# hub-proto02.net
KiCad netlist of a schematic drawn in EAGLE
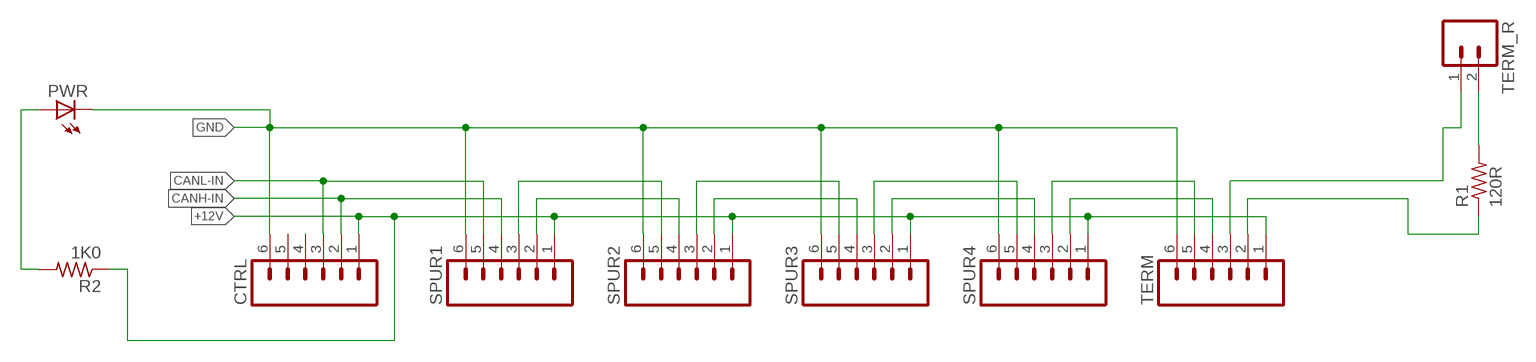
[diagram p0: schematic, sheet 1]

(export (version "E")
  (design (tool "Eeschema 10.0.6"))
  (components
    (comp (ref "CTRL")
      (value "M06")
      (footprint "eagle-import:06P")
      (libsource (lib "eagle-import") (part "M06"))
    )
    (comp (ref "PWR")
      (value "LED3MM")
      (footprint "eagle-import:LED3MM")
      (libsource (lib "eagle-import") (part "LED3MM"))
    )
    (comp (ref "R1")
      (value "120R")
      (footprint "eagle-import:0309_12")
      (libsource (lib "eagle-import") (part "R-US_0309/12"))
    )
    (comp (ref "R2")
      (value "1K0")
      (footprint "eagle-import:0309_12")
      (libsource (lib "eagle-import") (part "R-US_0309/12"))
    )
    (comp (ref "SPUR1")
      (value "M06")
      (footprint "eagle-import:06P")
      (libsource (lib "eagle-import") (part "M06"))
    )
    (comp (ref "SPUR2")
      (value "M06")
      (footprint "eagle-import:06P")
      (libsource (lib "eagle-import") (part "M06"))
    )
    (comp (ref "SPUR3")
      (value "M06")
      (footprint "eagle-import:06P")
      (libsource (lib "eagle-import") (part "M06"))
    )
    (comp (ref "SPUR4")
      (value "M06")
      (footprint "eagle-import:06P")
      (libsource (lib "eagle-import") (part "M06"))
    )
    (comp (ref "TERM")
      (value "M06")
      (footprint "eagle-import:06P")
      (libsource (lib "eagle-import") (part "M06"))
    )
    (comp (ref "TERM_R")
      (value "M02")
      (footprint "eagle-import:02P")
      (libsource (lib "eagle-import") (part "M02"))
    )
  )
  (nets
    (net (code "1") (name "+12V") (class "Default")
      (node (ref "CTRL") (pin "1") (pinfunction "1_1") (pintype "passive"))
      (node (ref "R2") (pin "1") (pinfunction "1_1") (pintype "passive"))
      (node (ref "SPUR1") (pin "1") (pinfunction "1_1") (pintype "passive"))
      (node (ref "SPUR2") (pin "1") (pinfunction "1_1") (pintype "passive"))
      (node (ref "SPUR3") (pin "1") (pinfunction "1_1") (pintype "passive"))
      (node (ref "SPUR4") (pin "1") (pinfunction "1_1") (pintype "passive"))
      (node (ref "TERM") (pin "1") (pinfunction "1_1") (pintype "passive"))
    )
    (net (code "2") (name "CANH-IN") (class "Default")
      (node (ref "CTRL") (pin "2") (pinfunction "2_2") (pintype "passive"))
      (node (ref "SPUR1") (pin "4") (pinfunction "4_4") (pintype "passive"))
    )
    (net (code "3") (name "CANL-IN") (class "Default")
      (node (ref "CTRL") (pin "3") (pinfunction "3_3") (pintype "passive"))
      (node (ref "SPUR1") (pin "5") (pinfunction "5_5") (pintype "passive"))
    )
    (net (code "4") (name "GND") (class "Default")
      (node (ref "CTRL") (pin "6") (pinfunction "6_6") (pintype "passive"))
      (node (ref "PWR") (pin "K") (pinfunction "C_K") (pintype "passive"))
      (node (ref "SPUR1") (pin "6") (pinfunction "6_6") (pintype "passive"))
      (node (ref "SPUR2") (pin "6") (pinfunction "6_6") (pintype "passive"))
      (node (ref "SPUR3") (pin "6") (pinfunction "6_6") (pintype "passive"))
      (node (ref "SPUR4") (pin "6") (pinfunction "6_6") (pintype "passive"))
      (node (ref "TERM") (pin "6") (pinfunction "6_6") (pintype "passive"))
    )
    (net (code "5") (name "Net-(PWR-PadA)") (class "Default")
      (node (ref "PWR") (pin "A") (pinfunction "A_A") (pintype "passive"))
      (node (ref "R2") (pin "2") (pinfunction "2_2") (pintype "passive"))
    )
    (net (code "6") (name "Net-(R1-Pad1)") (class "Default")
      (node (ref "R1") (pin "1") (pinfunction "1_1") (pintype "passive"))
      (node (ref "TERM") (pin "2") (pinfunction "2_2") (pintype "passive"))
    )
    (net (code "7") (name "Net-(R1-Pad2)") (class "Default")
      (node (ref "R1") (pin "2") (pinfunction "2_2") (pintype "passive"))
      (node (ref "TERM_R") (pin "2") (pinfunction "2_2") (pintype "passive"))
    )
    (net (code "8") (name "Net-(SPUR1-Pad2)") (class "Default")
      (node (ref "SPUR1") (pin "2") (pinfunction "2_2") (pintype "passive"))
      (node (ref "SPUR2") (pin "4") (pinfunction "4_4") (pintype "passive"))
    )
    (net (code "9") (name "Net-(SPUR1-Pad3)") (class "Default")
      (node (ref "SPUR1") (pin "3") (pinfunction "3_3") (pintype "passive"))
      (node (ref "SPUR2") (pin "5") (pinfunction "5_5") (pintype "passive"))
    )
    (net (code "10") (name "Net-(SPUR2-Pad2)") (class "Default")
      (node (ref "SPUR2") (pin "2") (pinfunction "2_2") (pintype "passive"))
      (node (ref "SPUR3") (pin "4") (pinfunction "4_4") (pintype "passive"))
    )
    (net (code "11") (name "Net-(SPUR2-Pad3)") (class "Default")
      (node (ref "SPUR2") (pin "3") (pinfunction "3_3") (pintype "passive"))
      (node (ref "SPUR3") (pin "5") (pinfunction "5_5") (pintype "passive"))
    )
    (net (code "12") (name "Net-(SPUR3-Pad2)") (class "Default")
      (node (ref "SPUR3") (pin "2") (pinfunction "2_2") (pintype "passive"))
      (node (ref "SPUR4") (pin "4") (pinfunction "4_4") (pintype "passive"))
    )
    (net (code "13") (name "Net-(SPUR3-Pad3)") (class "Default")
      (node (ref "SPUR3") (pin "3") (pinfunction "3_3") (pintype "passive"))
      (node (ref "SPUR4") (pin "5") (pinfunction "5_5") (pintype "passive"))
    )
    (net (code "14") (name "Net-(SPUR4-Pad2)") (class "Default")
      (node (ref "SPUR4") (pin "2") (pinfunction "2_2") (pintype "passive"))
      (node (ref "TERM") (pin "4") (pinfunction "4_4") (pintype "passive"))
    )
    (net (code "15") (name "Net-(SPUR4-Pad3)") (class "Default")
      (node (ref "SPUR4") (pin "3") (pinfunction "3_3") (pintype "passive"))
      (node (ref "TERM") (pin "5") (pinfunction "5_5") (pintype "passive"))
    )
    (net (code "16") (name "Net-(TERM-Pad3)") (class "Default")
      (node (ref "TERM") (pin "3") (pinfunction "3_3") (pintype "passive"))
      (node (ref "TERM_R") (pin "1") (pinfunction "1_1") (pintype "passive"))
    )
    (net (code "17") (name "unconnected-(CTRL-Pad4)") (class "Default")
      (node (ref "CTRL") (pin "4") (pinfunction "4_4") (pintype "passive"))
    )
    (net (code "18") (name "unconnected-(CTRL-Pad5)") (class "Default")
      (node (ref "CTRL") (pin "5") (pinfunction "5_5") (pintype "passive"))
    )
  )
)
